# ng-beacon-mdbt42-conn.net
KiCad netlist of a schematic drawn in EAGLE
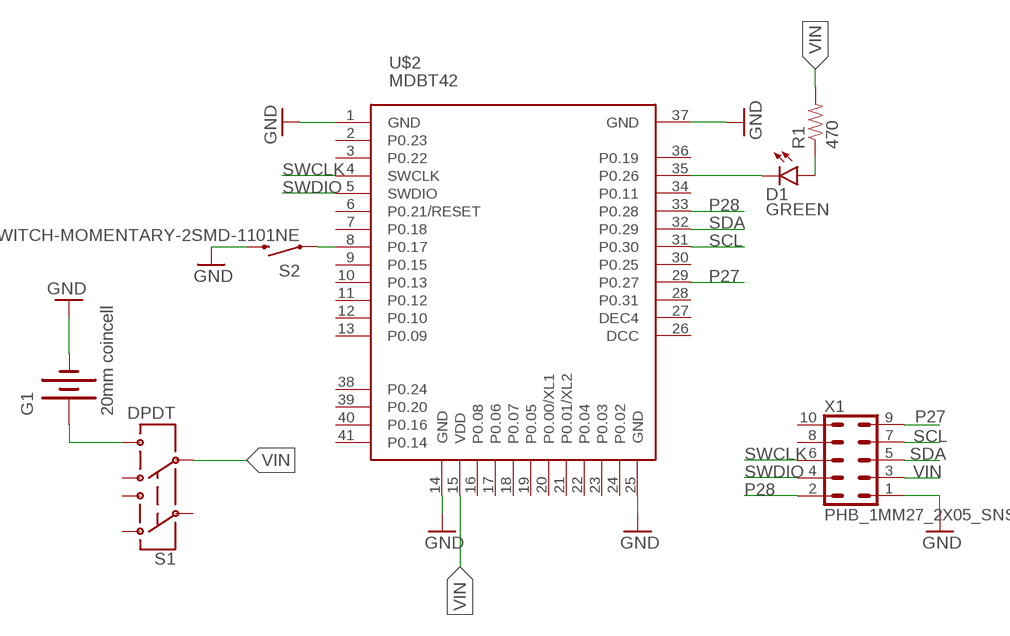
[diagram p0: schematic, sheet 1]

(export (version "E")
  (design (tool "Eeschema 10.0.6"))
  (components
    (comp (ref "D1")
      (value "GREEN")
      (footprint "eagle-import:LED-0603")
      (libsource (lib "eagle-import") (part "LED-GREEN0603"))
    )
    (comp (ref "G1")
      (value "20mm coincell")
      (footprint "eagle-import:BATTCON_20MM_4LEGS")
      (libsource (lib "eagle-import") (part "BATTERY20MM_4LEGS"))
    )
    (comp (ref "R1")
      (value "470")
      (footprint "eagle-import:0603-RES")
      (libsource (lib "eagle-import") (part "470OHM1/10W1%(0603)"))
    )
    (comp (ref "S1")
      (value "DPDT")
      (footprint "eagle-import:AYZ0202")
      (libsource (lib "eagle-import") (part "SWITCH-DPDTAYZ0202"))
    )
    (comp (ref "S2")
      (value "SWITCH-MOMENTARY-2SMD-1101NE")
      (footprint "eagle-import:TACTILE-SWITCH-1101NE")
      (libsource (lib "eagle-import") (part "SWITCH-MOMENTARY-2SMD-1101NE"))
    )
    (comp (ref "U$2")
      (value "MDBT42")
      (footprint "eagle-import:MDBT42")
      (libsource (lib "eagle-import") (part "MDBT42"))
    )
    (comp (ref "X1")
      (value "PHB_1MM27_2X05_SNS")
      (footprint "eagle-import:PHB_1MM27_2X05_SNS")
      (libsource (lib "eagle-import") (part "PHB_1MM27_2X05_SNS"))
    )
  )
  (nets
    (net (code "1") (name "/P27") (class "Default")
      (node (ref "U$2") (pin "29") (pinfunction "P0.27_29") (pintype "bidirectional"))
      (node (ref "X1") (pin "9") (pinfunction "9_9") (pintype "passive"))
    )
    (net (code "2") (name "/P28") (class "Default")
      (node (ref "U$2") (pin "33") (pinfunction "P0.28_33") (pintype "bidirectional"))
      (node (ref "X1") (pin "2") (pinfunction "2_2") (pintype "passive"))
    )
    (net (code "3") (name "/SCL") (class "Default")
      (node (ref "U$2") (pin "31") (pinfunction "P0.30_31") (pintype "bidirectional"))
      (node (ref "X1") (pin "7") (pinfunction "7_7") (pintype "passive"))
    )
    (net (code "4") (name "/SDA") (class "Default")
      (node (ref "U$2") (pin "32") (pinfunction "P0.29_32") (pintype "bidirectional"))
      (node (ref "X1") (pin "5") (pinfunction "5_5") (pintype "passive"))
    )
    (net (code "5") (name "/SWCLK") (class "Default")
      (node (ref "U$2") (pin "4") (pinfunction "SWCLK_4") (pintype "bidirectional"))
      (node (ref "X1") (pin "6") (pinfunction "6_6") (pintype "passive"))
    )
    (net (code "6") (name "/SWDIO") (class "Default")
      (node (ref "U$2") (pin "5") (pinfunction "SWDIO_5") (pintype "bidirectional"))
      (node (ref "X1") (pin "4") (pinfunction "4_4") (pintype "passive"))
    )
    (net (code "7") (name "GND") (class "Default")
      (node (ref "G1") (pin "NEGATIVE") (pinfunction "-_NEGATIVE") (pintype "power_in"))
      (node (ref "S2") (pin "2") (pinfunction "2_2") (pintype "passive"))
      (node (ref "U$2") (pin "1") (pinfunction "GND_1") (pintype "bidirectional"))
      (node (ref "U$2") (pin "14") (pinfunction "GND_14") (pintype "bidirectional"))
      (node (ref "U$2") (pin "25") (pinfunction "GND_25") (pintype "bidirectional"))
      (node (ref "U$2") (pin "37") (pinfunction "GND_37") (pintype "bidirectional"))
      (node (ref "X1") (pin "1") (pinfunction "1_1") (pintype "passive"))
    )
    (net (code "8") (name "Net-(D1-PadA)") (class "Default")
      (node (ref "D1") (pin "A") (pinfunction "A_A") (pintype "passive"))
      (node (ref "R1") (pin "1") (pinfunction "1_1") (pintype "passive"))
    )
    (net (code "9") (name "Net-(G1-+-PadPOSITIVE@1)") (class "Default")
      (node (ref "G1") (pin "POSITIVE@1") (pinfunction "+_POSITIVE@1") (pintype "power_in"))
      (node (ref "G1") (pin "POSITIVE@2") (pinfunction "+_POSITIVE@2") (pintype "power_in"))
      (node (ref "G1") (pin "POSITIVE@3") (pinfunction "+_POSITIVE@3") (pintype "power_in"))
      (node (ref "G1") (pin "POSITIVE@4") (pinfunction "+_POSITIVE@4") (pintype "power_in"))
      (node (ref "S1") (pin "6") (pinfunction "6_6") (pintype "bidirectional"))
    )
    (net (code "10") (name "Net-(U$2-P0.17)") (class "Default")
      (node (ref "S2") (pin "1") (pinfunction "1_1") (pintype "passive"))
      (node (ref "U$2") (pin "8") (pinfunction "P0.17_8") (pintype "bidirectional"))
    )
    (net (code "11") (name "Net-(U$2-P0.26)") (class "Default")
      (node (ref "D1") (pin "C") (pinfunction "C_C") (pintype "passive"))
      (node (ref "U$2") (pin "35") (pinfunction "P0.26_35") (pintype "bidirectional"))
    )
    (net (code "12") (name "VIN") (class "Default")
      (node (ref "R1") (pin "2") (pinfunction "2_2") (pintype "passive"))
      (node (ref "S1") (pin "5") (pinfunction "5_5") (pintype "bidirectional"))
      (node (ref "U$2") (pin "15") (pinfunction "VDD_15") (pintype "bidirectional"))
      (node (ref "X1") (pin "3") (pinfunction "3_3") (pintype "passive"))
    )
    (net (code "13") (name "unconnected-(S1-Pad1)") (class "Default")
      (node (ref "S1") (pin "1") (pinfunction "1_1") (pintype "bidirectional"))
    )
    (net (code "14") (name "unconnected-(S1-Pad2)") (class "Default")
      (node (ref "S1") (pin "2") (pinfunction "2_2") (pintype "bidirectional"))
    )
    (net (code "15") (name "unconnected-(S1-Pad3)") (class "Default")
      (node (ref "S1") (pin "3") (pinfunction "3_3") (pintype "bidirectional"))
    )
    (net (code "16") (name "unconnected-(S1-Pad4)") (class "Default")
      (node (ref "S1") (pin "4") (pinfunction "4_4") (pintype "bidirectional"))
    )
    (net (code "17") (name "unconnected-(U$2-DCC-Pad26)") (class "Default")
      (node (ref "U$2") (pin "26") (pinfunction "DCC_26") (pintype "bidirectional"))
    )
    (net (code "18") (name "unconnected-(U$2-DEC4-Pad27)") (class "Default")
      (node (ref "U$2") (pin "27") (pinfunction "DEC4_27") (pintype "bidirectional"))
    )
    (net (code "19") (name "unconnected-(U$2-P0.00{slash}XL1-Pad20)") (class "Default")
      (node (ref "U$2") (pin "20") (pinfunction "P0.00/XL1_20") (pintype "bidirectional"))
    )
    (net (code "20") (name "unconnected-(U$2-P0.01{slash}XL2-Pad21)") (class "Default")
      (node (ref "U$2") (pin "21") (pinfunction "P0.01/XL2_21") (pintype "bidirectional"))
    )
    (net (code "21") (name "unconnected-(U$2-P0.02-Pad24)") (class "Default")
      (node (ref "U$2") (pin "24") (pinfunction "P0.02_24") (pintype "bidirectional"))
    )
    (net (code "22") (name "unconnected-(U$2-P0.03-Pad23)") (class "Default")
      (node (ref "U$2") (pin "23") (pinfunction "P0.03_23") (pintype "bidirectional"))
    )
    (net (code "23") (name "unconnected-(U$2-P0.04-Pad22)") (class "Default")
      (node (ref "U$2") (pin "22") (pinfunction "P0.04_22") (pintype "bidirectional"))
    )
    (net (code "24") (name "unconnected-(U$2-P0.05-Pad19)") (class "Default")
      (node (ref "U$2") (pin "19") (pinfunction "P0.05_19") (pintype "bidirectional"))
    )
    (net (code "25") (name "unconnected-(U$2-P0.06-Pad17)") (class "Default")
      (node (ref "U$2") (pin "17") (pinfunction "P0.06_17") (pintype "bidirectional"))
    )
    (net (code "26") (name "unconnected-(U$2-P0.07-Pad18)") (class "Default")
      (node (ref "U$2") (pin "18") (pinfunction "P0.07_18") (pintype "bidirectional"))
    )
    (net (code "27") (name "unconnected-(U$2-P0.08-Pad16)") (class "Default")
      (node (ref "U$2") (pin "16") (pinfunction "P0.08_16") (pintype "bidirectional"))
    )
    (net (code "28") (name "unconnected-(U$2-P0.09-Pad13)") (class "Default")
      (node (ref "U$2") (pin "13") (pinfunction "P0.09_13") (pintype "bidirectional"))
    )
    (net (code "29") (name "unconnected-(U$2-P0.10-Pad12)") (class "Default")
      (node (ref "U$2") (pin "12") (pinfunction "P0.10_12") (pintype "bidirectional"))
    )
    (net (code "30") (name "unconnected-(U$2-P0.11-Pad34)") (class "Default")
      (node (ref "U$2") (pin "34") (pinfunction "P0.11_34") (pintype "bidirectional"))
    )
    (net (code "31") (name "unconnected-(U$2-P0.12-Pad11)") (class "Default")
      (node (ref "U$2") (pin "11") (pinfunction "P0.12_11") (pintype "bidirectional"))
    )
    (net (code "32") (name "unconnected-(U$2-P0.13-Pad10)") (class "Default")
      (node (ref "U$2") (pin "10") (pinfunction "P0.13_10") (pintype "bidirectional"))
    )
    (net (code "33") (name "unconnected-(U$2-P0.14-Pad41)") (class "Default")
      (node (ref "U$2") (pin "41") (pinfunction "P0.14_41") (pintype "bidirectional"))
    )
    (net (code "34") (name "unconnected-(U$2-P0.15-Pad9)") (class "Default")
      (node (ref "U$2") (pin "9") (pinfunction "P0.15_9") (pintype "bidirectional"))
    )
    (net (code "35") (name "unconnected-(U$2-P0.16-Pad40)") (class "Default")
      (node (ref "U$2") (pin "40") (pinfunction "P0.16_40") (pintype "bidirectional"))
    )
    (net (code "36") (name "unconnected-(U$2-P0.18-Pad7)") (class "Default")
      (node (ref "U$2") (pin "7") (pinfunction "P0.18_7") (pintype "bidirectional"))
    )
    (net (code "37") (name "unconnected-(U$2-P0.19-Pad36)") (class "Default")
      (node (ref "U$2") (pin "36") (pinfunction "P0.19_36") (pintype "bidirectional"))
    )
    (net (code "38") (name "unconnected-(U$2-P0.20-Pad39)") (class "Default")
      (node (ref "U$2") (pin "39") (pinfunction "P0.20_39") (pintype "bidirectional"))
    )
    (net (code "39") (name "unconnected-(U$2-P0.21{slash}RESET-Pad6)") (class "Default")
      (node (ref "U$2") (pin "6") (pinfunction "P0.21/RESET_6") (pintype "bidirectional"))
    )
    (net (code "40") (name "unconnected-(U$2-P0.22-Pad3)") (class "Default")
      (node (ref "U$2") (pin "3") (pinfunction "P0.22_3") (pintype "bidirectional"))
    )
    (net (code "41") (name "unconnected-(U$2-P0.23-Pad2)") (class "Default")
      (node (ref "U$2") (pin "2") (pinfunction "P0.23_2") (pintype "bidirectional"))
    )
    (net (code "42") (name "unconnected-(U$2-P0.24-Pad38)") (class "Default")
      (node (ref "U$2") (pin "38") (pinfunction "P0.24_38") (pintype "bidirectional"))
    )
    (net (code "43") (name "unconnected-(U$2-P0.25-Pad30)") (class "Default")
      (node (ref "U$2") (pin "30") (pinfunction "P0.25_30") (pintype "bidirectional"))
    )
    (net (code "44") (name "unconnected-(U$2-P0.31-Pad28)") (class "Default")
      (node (ref "U$2") (pin "28") (pinfunction "P0.31_28") (pintype "bidirectional"))
    )
    (net (code "45") (name "unconnected-(X1-Pad8)") (class "Default")
      (node (ref "X1") (pin "8") (pinfunction "8_8") (pintype "passive"))
    )
    (net (code "46") (name "unconnected-(X1-Pad10)") (class "Default")
      (node (ref "X1") (pin "10") (pinfunction "10_10") (pintype "passive"))
    )
  )
)
